# Brigid_control_board.net
KiCad netlist of a schematic drawn in EAGLE
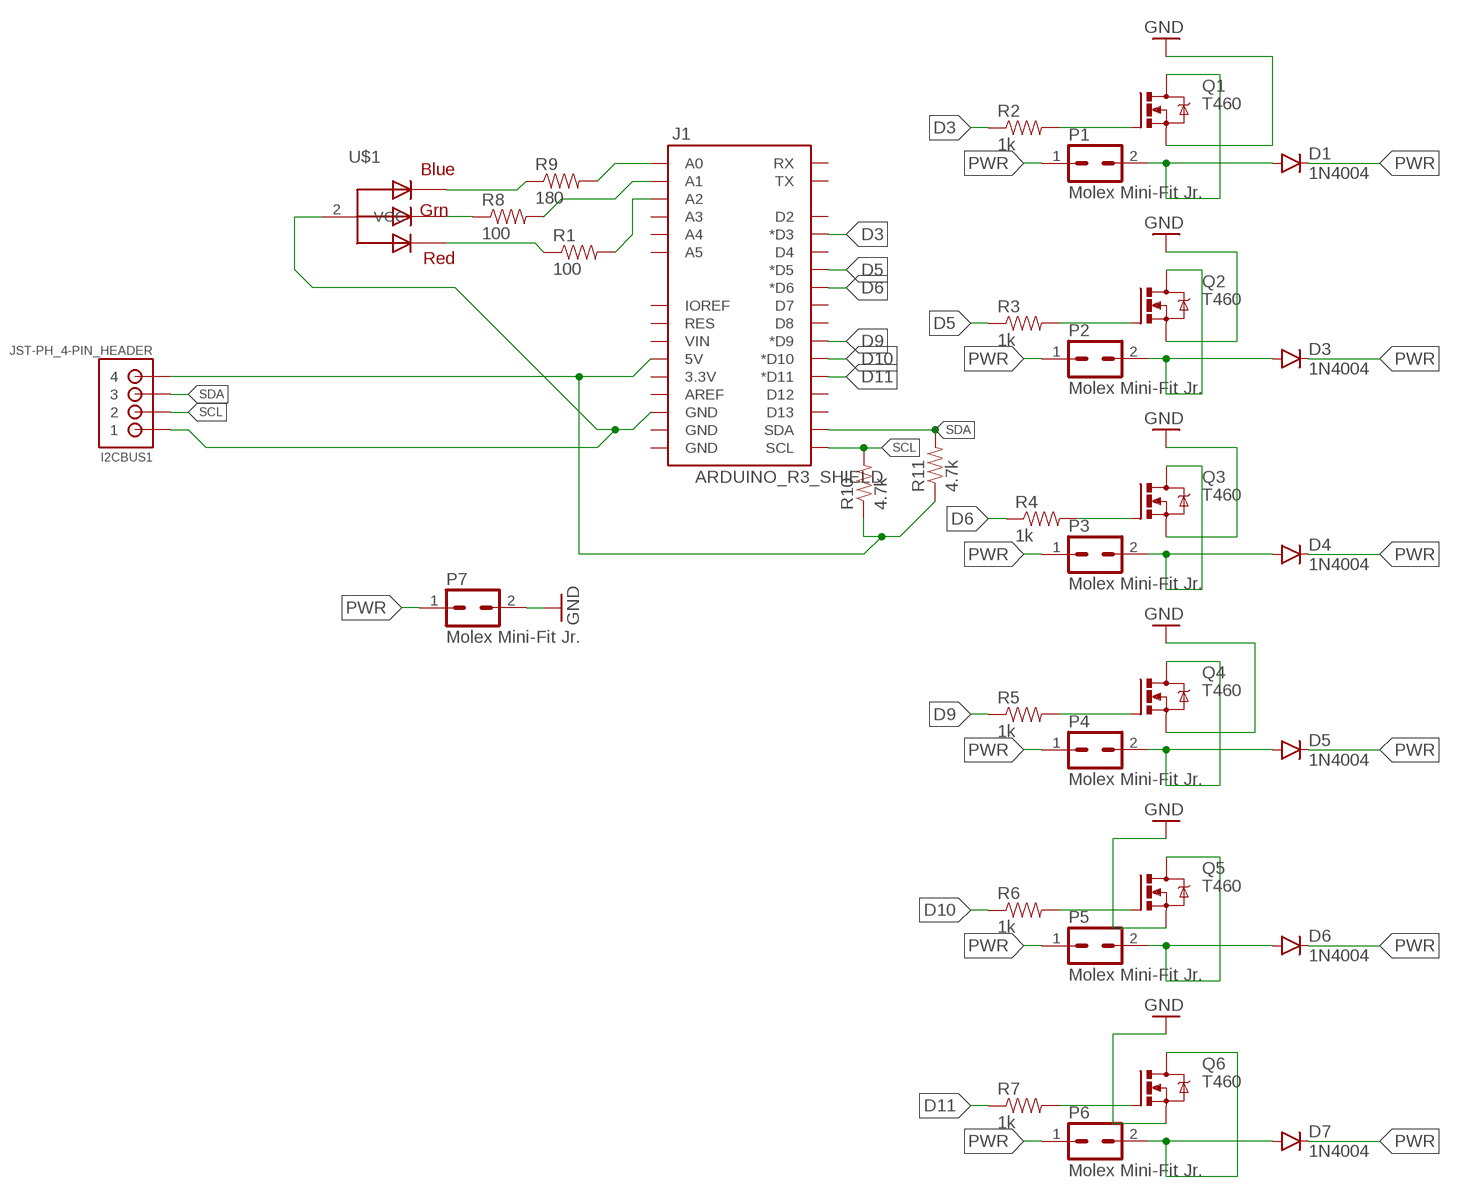
[diagram p0: schematic, sheet 1]

(export (version "E")
  (design (tool "Eeschema 10.0.6"))
  (components
    (comp (ref "D1")
      (value "1N4004")
      (footprint "eagle-import:DIODE-1N4001")
      (libsource (lib "eagle-import") (part "DIODEPTH"))
    )
    (comp (ref "D3")
      (value "1N4004")
      (footprint "eagle-import:DIODE-1N4001")
      (libsource (lib "eagle-import") (part "DIODEPTH"))
    )
    (comp (ref "D4")
      (value "1N4004")
      (footprint "eagle-import:DIODE-1N4001")
      (libsource (lib "eagle-import") (part "DIODEPTH"))
    )
    (comp (ref "D5")
      (value "1N4004")
      (footprint "eagle-import:DIODE-1N4001")
      (libsource (lib "eagle-import") (part "DIODEPTH"))
    )
    (comp (ref "D6")
      (value "1N4004")
      (footprint "eagle-import:DIODE-1N4001")
      (libsource (lib "eagle-import") (part "DIODEPTH"))
    )
    (comp (ref "D7")
      (value "1N4004")
      (footprint "eagle-import:DIODE-1N4001")
      (libsource (lib "eagle-import") (part "DIODEPTH"))
    )
    (comp (ref "I2CBUS1")
      (value "JST-PH_4-PIN_HEADER")
      (footprint "eagle-import:JST_B4B-PH_HEADER")
      (libsource (lib "eagle-import") (part "JST-PH_4-PIN_HEADER"))
    )
    (comp (ref "J1")
      (value "ARDUINO_R3_SHIELD")
      (footprint "eagle-import:UNO_R3_SHIELD")
      (libsource (lib "eagle-import") (part "ARDUINO_R3_SHIELD"))
    )
    (comp (ref "P1")
      (value "Molex Mini-Fit Jr.")
      (footprint "eagle-import:39-30-_02_")
      (libsource (lib "eagle-import") (part "39-30-?02?"))
    )
    (comp (ref "P2")
      (value "Molex Mini-Fit Jr.")
      (footprint "eagle-import:39-30-_02_")
      (libsource (lib "eagle-import") (part "39-30-?02?"))
    )
    (comp (ref "P3")
      (value "Molex Mini-Fit Jr.")
      (footprint "eagle-import:39-30-_02_")
      (libsource (lib "eagle-import") (part "39-30-?02?"))
    )
    (comp (ref "P4")
      (value "Molex Mini-Fit Jr.")
      (footprint "eagle-import:39-30-_02_")
      (libsource (lib "eagle-import") (part "39-30-?02?"))
    )
    (comp (ref "P5")
      (value "Molex Mini-Fit Jr.")
      (footprint "eagle-import:39-30-_02_")
      (libsource (lib "eagle-import") (part "39-30-?02?"))
    )
    (comp (ref "P6")
      (value "Molex Mini-Fit Jr.")
      (footprint "eagle-import:39-30-_02_")
      (libsource (lib "eagle-import") (part "39-30-?02?"))
    )
    (comp (ref "P7")
      (value "Molex Mini-Fit Jr.")
      (footprint "eagle-import:39-30-_02_")
      (libsource (lib "eagle-import") (part "39-30-?02?"))
    )
    (comp (ref "Q1")
      (value "T460")
      (footprint "eagle-import:TO220BV")
      (libsource (lib "eagle-import") (part "IRF540"))
    )
    (comp (ref "Q2")
      (value "T460")
      (footprint "eagle-import:TO220BV")
      (libsource (lib "eagle-import") (part "IRF540"))
    )
    (comp (ref "Q3")
      (value "T460")
      (footprint "eagle-import:TO220BV")
      (libsource (lib "eagle-import") (part "IRF540"))
    )
    (comp (ref "Q4")
      (value "T460")
      (footprint "eagle-import:TO220BV")
      (libsource (lib "eagle-import") (part "IRF540"))
    )
    (comp (ref "Q5")
      (value "T460")
      (footprint "eagle-import:TO220BV")
      (libsource (lib "eagle-import") (part "IRF540"))
    )
    (comp (ref "Q6")
      (value "T460")
      (footprint "eagle-import:TO220BV")
      (libsource (lib "eagle-import") (part "IRF540"))
    )
    (comp (ref "R1")
      (value "100")
      (footprint "eagle-import:AXIAL-0.3EZ")
      (libsource (lib "eagle-import") (part "RESISTOREZ"))
    )
    (comp (ref "R2")
      (value "1k")
      (footprint "eagle-import:AXIAL-0.3EZ")
      (libsource (lib "eagle-import") (part "RESISTOREZ"))
    )
    (comp (ref "R3")
      (value "1k")
      (footprint "eagle-import:AXIAL-0.3EZ")
      (libsource (lib "eagle-import") (part "RESISTOREZ"))
    )
    (comp (ref "R4")
      (value "1k")
      (footprint "eagle-import:AXIAL-0.3EZ")
      (libsource (lib "eagle-import") (part "RESISTOREZ"))
    )
    (comp (ref "R5")
      (value "1k")
      (footprint "eagle-import:AXIAL-0.3EZ")
      (libsource (lib "eagle-import") (part "RESISTOREZ"))
    )
    (comp (ref "R6")
      (value "1k")
      (footprint "eagle-import:AXIAL-0.3EZ")
      (libsource (lib "eagle-import") (part "RESISTOREZ"))
    )
    (comp (ref "R7")
      (value "1k")
      (footprint "eagle-import:AXIAL-0.3EZ")
      (libsource (lib "eagle-import") (part "RESISTOREZ"))
    )
    (comp (ref "R8")
      (value "100")
      (footprint "eagle-import:AXIAL-0.3EZ")
      (libsource (lib "eagle-import") (part "RESISTOREZ"))
    )
    (comp (ref "R9")
      (value "180")
      (footprint "eagle-import:AXIAL-0.3EZ")
      (libsource (lib "eagle-import") (part "RESISTOREZ"))
    )
    (comp (ref "R10")
      (value "4.7k")
      (footprint "eagle-import:AXIAL-0.3EZ")
      (libsource (lib "eagle-import") (part "RESISTOREZ"))
    )
    (comp (ref "R11")
      (value "4.7k")
      (footprint "eagle-import:AXIAL-0.3EZ")
      (libsource (lib "eagle-import") (part "RESISTOREZ"))
    )
    (comp (ref "U$1")
      (value "RGB LED")
      (footprint "eagle-import:LED5MMRGB")
      (libsource (lib "eagle-import") (part "RGBLED_CA"))
    )
  )
  (nets
    (net (code "1") (name "D3") (class "Default")
      (node (ref "J1") (pin "D3") (pinfunction "*D3_D3") (pintype "bidirectional"))
      (node (ref "R2") (pin "P$1") (pinfunction "1_P$1") (pintype "passive"))
    )
    (net (code "2") (name "D5") (class "Default")
      (node (ref "J1") (pin "D5") (pinfunction "*D5_D5") (pintype "bidirectional"))
      (node (ref "R3") (pin "P$1") (pinfunction "1_P$1") (pintype "passive"))
    )
    (net (code "3") (name "D6") (class "Default")
      (node (ref "J1") (pin "D6") (pinfunction "*D6_D6") (pintype "bidirectional"))
      (node (ref "R4") (pin "P$1") (pinfunction "1_P$1") (pintype "passive"))
    )
    (net (code "4") (name "D9") (class "Default")
      (node (ref "J1") (pin "D9") (pinfunction "*D9_D9") (pintype "bidirectional"))
      (node (ref "R5") (pin "P$1") (pinfunction "1_P$1") (pintype "passive"))
    )
    (net (code "5") (name "D10") (class "Default")
      (node (ref "J1") (pin "D10") (pinfunction "*D10_D10") (pintype "bidirectional"))
      (node (ref "R6") (pin "P$1") (pinfunction "1_P$1") (pintype "passive"))
    )
    (net (code "6") (name "D11") (class "Default")
      (node (ref "J1") (pin "D11") (pinfunction "*D11_D11") (pintype "bidirectional"))
      (node (ref "R7") (pin "P$1") (pinfunction "1_P$1") (pintype "passive"))
    )
    (net (code "7") (name "GND") (class "Default")
      (node (ref "P7") (pin "2") (pinfunction "2_2") (pintype "passive"))
      (node (ref "Q1") (pin "S") (pinfunction "S_S") (pintype "passive"))
      (node (ref "Q2") (pin "S") (pinfunction "S_S") (pintype "passive"))
      (node (ref "Q3") (pin "S") (pinfunction "S_S") (pintype "passive"))
      (node (ref "Q4") (pin "S") (pinfunction "S_S") (pintype "passive"))
      (node (ref "Q5") (pin "S") (pinfunction "S_S") (pintype "passive"))
      (node (ref "Q6") (pin "S") (pinfunction "S_S") (pintype "passive"))
    )
    (net (code "8") (name "Net-(D1-PadA)") (class "Default")
      (node (ref "D1") (pin "A") (pinfunction "A_A") (pintype "passive"))
      (node (ref "P1") (pin "2") (pinfunction "2_2") (pintype "passive"))
      (node (ref "Q1") (pin "D") (pinfunction "D_D") (pintype "passive"))
    )
    (net (code "9") (name "Net-(D3-PadA)") (class "Default")
      (node (ref "D3") (pin "A") (pinfunction "A_A") (pintype "passive"))
      (node (ref "P2") (pin "2") (pinfunction "2_2") (pintype "passive"))
      (node (ref "Q2") (pin "D") (pinfunction "D_D") (pintype "passive"))
    )
    (net (code "10") (name "Net-(D4-PadA)") (class "Default")
      (node (ref "D4") (pin "A") (pinfunction "A_A") (pintype "passive"))
      (node (ref "P3") (pin "2") (pinfunction "2_2") (pintype "passive"))
      (node (ref "Q3") (pin "D") (pinfunction "D_D") (pintype "passive"))
    )
    (net (code "11") (name "Net-(D5-PadA)") (class "Default")
      (node (ref "D5") (pin "A") (pinfunction "A_A") (pintype "passive"))
      (node (ref "P4") (pin "2") (pinfunction "2_2") (pintype "passive"))
      (node (ref "Q4") (pin "D") (pinfunction "D_D") (pintype "passive"))
    )
    (net (code "12") (name "Net-(D6-PadA)") (class "Default")
      (node (ref "D6") (pin "A") (pinfunction "A_A") (pintype "passive"))
      (node (ref "P5") (pin "2") (pinfunction "2_2") (pintype "passive"))
      (node (ref "Q5") (pin "D") (pinfunction "D_D") (pintype "passive"))
    )
    (net (code "13") (name "Net-(D7-PadA)") (class "Default")
      (node (ref "D7") (pin "A") (pinfunction "A_A") (pintype "passive"))
      (node (ref "P6") (pin "2") (pinfunction "2_2") (pintype "passive"))
      (node (ref "Q6") (pin "D") (pinfunction "D_D") (pintype "passive"))
    )
    (net (code "14") (name "Net-(I2CBUS1-1)") (class "Default")
      (node (ref "I2CBUS1") (pin "P1") (pinfunction "1_P1") (pintype "bidirectional"))
      (node (ref "J1") (pin "GND@2") (pinfunction "GND_GND@2") (pintype "bidirectional"))
      (node (ref "U$1") (pin "2") (pinfunction "VCC_2") (pintype "bidirectional"))
    )
    (net (code "15") (name "Net-(I2CBUS1-4)") (class "Default")
      (node (ref "I2CBUS1") (pin "P4") (pinfunction "4_P4") (pintype "bidirectional"))
      (node (ref "J1") (pin "5V") (pinfunction "5V_5V") (pintype "bidirectional"))
      (node (ref "R10") (pin "P$1") (pinfunction "1_P$1") (pintype "passive"))
      (node (ref "R11") (pin "P$1") (pinfunction "1_P$1") (pintype "passive"))
    )
    (net (code "16") (name "Net-(R1-1)") (class "Default")
      (node (ref "R1") (pin "P$1") (pinfunction "1_P$1") (pintype "passive"))
      (node (ref "U$1") (pin "1") (pinfunction "RED_1") (pintype "bidirectional"))
    )
    (net (code "17") (name "Net-(R1-2)") (class "Default")
      (node (ref "J1") (pin "A2") (pinfunction "A2_A2") (pintype "bidirectional"))
      (node (ref "R1") (pin "P$2") (pinfunction "2_P$2") (pintype "passive"))
    )
    (net (code "18") (name "Net-(R2-2)") (class "Default")
      (node (ref "Q1") (pin "G") (pinfunction "G_G") (pintype "passive"))
      (node (ref "R2") (pin "P$2") (pinfunction "2_P$2") (pintype "passive"))
    )
    (net (code "19") (name "Net-(R3-2)") (class "Default")
      (node (ref "Q2") (pin "G") (pinfunction "G_G") (pintype "passive"))
      (node (ref "R3") (pin "P$2") (pinfunction "2_P$2") (pintype "passive"))
    )
    (net (code "20") (name "Net-(R4-2)") (class "Default")
      (node (ref "Q3") (pin "G") (pinfunction "G_G") (pintype "passive"))
      (node (ref "R4") (pin "P$2") (pinfunction "2_P$2") (pintype "passive"))
    )
    (net (code "21") (name "Net-(R5-2)") (class "Default")
      (node (ref "Q4") (pin "G") (pinfunction "G_G") (pintype "passive"))
      (node (ref "R5") (pin "P$2") (pinfunction "2_P$2") (pintype "passive"))
    )
    (net (code "22") (name "Net-(R6-2)") (class "Default")
      (node (ref "Q5") (pin "G") (pinfunction "G_G") (pintype "passive"))
      (node (ref "R6") (pin "P$2") (pinfunction "2_P$2") (pintype "passive"))
    )
    (net (code "23") (name "Net-(R7-2)") (class "Default")
      (node (ref "Q6") (pin "G") (pinfunction "G_G") (pintype "passive"))
      (node (ref "R7") (pin "P$2") (pinfunction "2_P$2") (pintype "passive"))
    )
    (net (code "24") (name "Net-(R8-1)") (class "Default")
      (node (ref "R8") (pin "P$1") (pinfunction "1_P$1") (pintype "passive"))
      (node (ref "U$1") (pin "3") (pinfunction "GREEN_3") (pintype "bidirectional"))
    )
    (net (code "25") (name "Net-(R8-2)") (class "Default")
      (node (ref "J1") (pin "A1") (pinfunction "A1_A1") (pintype "bidirectional"))
      (node (ref "R8") (pin "P$2") (pinfunction "2_P$2") (pintype "passive"))
    )
    (net (code "26") (name "Net-(R9-1)") (class "Default")
      (node (ref "R9") (pin "P$1") (pinfunction "1_P$1") (pintype "passive"))
      (node (ref "U$1") (pin "4") (pinfunction "BLUE_4") (pintype "bidirectional"))
    )
    (net (code "27") (name "Net-(R9-2)") (class "Default")
      (node (ref "J1") (pin "A0") (pinfunction "A0_A0") (pintype "bidirectional"))
      (node (ref "R9") (pin "P$2") (pinfunction "2_P$2") (pintype "passive"))
    )
    (net (code "28") (name "PWR") (class "Default")
      (node (ref "D1") (pin "C") (pinfunction "C_C") (pintype "passive"))
      (node (ref "D3") (pin "C") (pinfunction "C_C") (pintype "passive"))
      (node (ref "D4") (pin "C") (pinfunction "C_C") (pintype "passive"))
      (node (ref "D5") (pin "C") (pinfunction "C_C") (pintype "passive"))
      (node (ref "D6") (pin "C") (pinfunction "C_C") (pintype "passive"))
      (node (ref "D7") (pin "C") (pinfunction "C_C") (pintype "passive"))
      (node (ref "P1") (pin "1") (pinfunction "1_1") (pintype "passive"))
      (node (ref "P2") (pin "1") (pinfunction "1_1") (pintype "passive"))
      (node (ref "P3") (pin "1") (pinfunction "1_1") (pintype "passive"))
      (node (ref "P4") (pin "1") (pinfunction "1_1") (pintype "passive"))
      (node (ref "P5") (pin "1") (pinfunction "1_1") (pintype "passive"))
      (node (ref "P6") (pin "1") (pinfunction "1_1") (pintype "passive"))
      (node (ref "P7") (pin "1") (pinfunction "1_1") (pintype "passive"))
    )
    (net (code "29") (name "SCL") (class "Default")
      (node (ref "I2CBUS1") (pin "P2") (pinfunction "2_P2") (pintype "bidirectional"))
      (node (ref "J1") (pin "SCL") (pinfunction "SCL_SCL") (pintype "bidirectional"))
      (node (ref "R10") (pin "P$2") (pinfunction "2_P$2") (pintype "passive"))
    )
    (net (code "30") (name "SDA") (class "Default")
      (node (ref "I2CBUS1") (pin "P3") (pinfunction "3_P3") (pintype "bidirectional"))
      (node (ref "J1") (pin "SDA") (pinfunction "SDA_SDA") (pintype "bidirectional"))
      (node (ref "R11") (pin "P$2") (pinfunction "2_P$2") (pintype "passive"))
    )
    (net (code "31") (name "unconnected-(J1-GND-PadGND@0)") (class "Default")
      (node (ref "J1") (pin "GND@0") (pinfunction "GND_GND@0") (pintype "bidirectional"))
    )
    (net (code "32") (name "unconnected-(J1-GND-PadGND@1)") (class "Default")
      (node (ref "J1") (pin "GND@1") (pinfunction "GND_GND@1") (pintype "bidirectional"))
    )
    (net (code "33") (name "unconnected-(J1-Pad3.3V)") (class "Default")
      (node (ref "J1") (pin "3.3V") (pinfunction "3.3V_3.3V") (pintype "bidirectional"))
    )
    (net (code "34") (name "unconnected-(J1-PadA3)") (class "Default")
      (node (ref "J1") (pin "A3") (pinfunction "A3_A3") (pintype "bidirectional"))
    )
    (net (code "35") (name "unconnected-(J1-PadA4)") (class "Default")
      (node (ref "J1") (pin "A4") (pinfunction "A4_A4") (pintype "bidirectional"))
    )
    (net (code "36") (name "unconnected-(J1-PadA5)") (class "Default")
      (node (ref "J1") (pin "A5") (pinfunction "A5_A5") (pintype "bidirectional"))
    )
    (net (code "37") (name "unconnected-(J1-PadAREF)") (class "Default")
      (node (ref "J1") (pin "AREF") (pinfunction "AREF_AREF") (pintype "bidirectional"))
    )
    (net (code "38") (name "unconnected-(J1-PadD2)") (class "Default")
      (node (ref "J1") (pin "D2") (pinfunction "D2_D2") (pintype "bidirectional"))
    )
    (net (code "39") (name "unconnected-(J1-PadD4)") (class "Default")
      (node (ref "J1") (pin "D4") (pinfunction "D4_D4") (pintype "bidirectional"))
    )
    (net (code "40") (name "unconnected-(J1-PadD7)") (class "Default")
      (node (ref "J1") (pin "D7") (pinfunction "D7_D7") (pintype "bidirectional"))
    )
    (net (code "41") (name "unconnected-(J1-PadD8)") (class "Default")
      (node (ref "J1") (pin "D8") (pinfunction "D8_D8") (pintype "bidirectional"))
    )
    (net (code "42") (name "unconnected-(J1-PadD12)") (class "Default")
      (node (ref "J1") (pin "D12") (pinfunction "D12_D12") (pintype "bidirectional"))
    )
    (net (code "43") (name "unconnected-(J1-PadD13)") (class "Default")
      (node (ref "J1") (pin "D13") (pinfunction "D13_D13") (pintype "bidirectional"))
    )
    (net (code "44") (name "unconnected-(J1-PadIOREF)") (class "Default")
      (node (ref "J1") (pin "IOREF") (pinfunction "IOREF_IOREF") (pintype "bidirectional"))
    )
    (net (code "45") (name "unconnected-(J1-PadRES)") (class "Default")
      (node (ref "J1") (pin "RES") (pinfunction "RES_RES") (pintype "bidirectional"))
    )
    (net (code "46") (name "unconnected-(J1-PadRX)") (class "Default")
      (node (ref "J1") (pin "RX") (pinfunction "RX_RX") (pintype "bidirectional"))
    )
    (net (code "47") (name "unconnected-(J1-PadTX)") (class "Default")
      (node (ref "J1") (pin "TX") (pinfunction "TX_TX") (pintype "bidirectional"))
    )
    (net (code "48") (name "unconnected-(J1-PadVIN)") (class "Default")
      (node (ref "J1") (pin "VIN") (pinfunction "VIN_VIN") (pintype "bidirectional"))
    )
  )
)
